# SR_latch.net
KiCad netlist of a schematic drawn in EAGLE
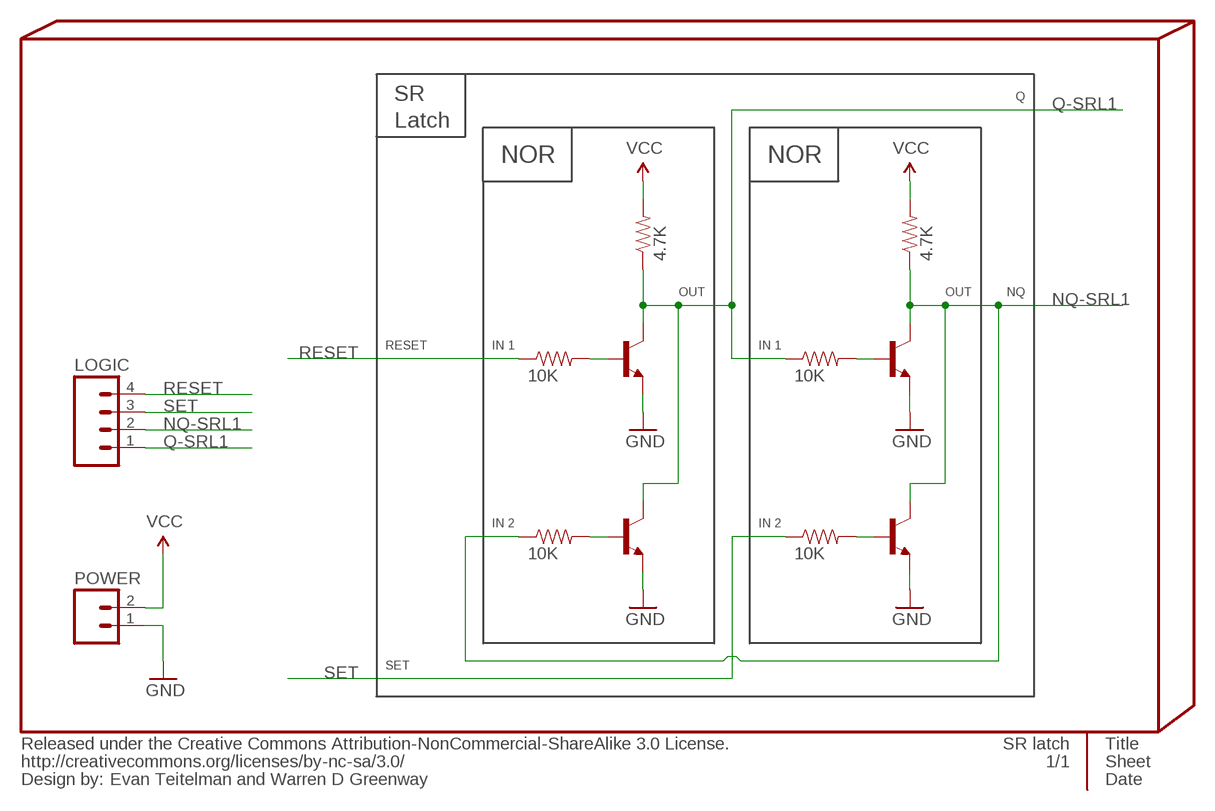
[diagram p0: schematic, sheet 1]

(export (version "E")
  (design (tool "Eeschema 10.0.6"))
  (components
    (comp (ref "INFO4")
      (value "Evan Teitelman and Warren D Greenway")
      (footprint "eagle-import:%CC-NC-SA")
      (libsource (lib "eagle-import") (part "%CC-NC-SA"))
    )
    (comp (ref "LOGIC")
      (value "M04PTH")
      (footprint "eagle-import:1X04")
      (libsource (lib "eagle-import") (part "M04PTH"))
    )
    (comp (ref "POWER")
      (value "M02PTH")
      (footprint "eagle-import:1X02")
      (libsource (lib "eagle-import") (part "M02PTH"))
    )
    (comp (ref "PUR-NOR1-SRL1")
      (value "4.7K")
      (footprint "eagle-import:0402-RES")
      (libsource (lib "eagle-import") (part "RESISTOR0402-RES"))
    )
    (comp (ref "PUR-NOR2-SRL1")
      (value "4.7K")
      (footprint "eagle-import:0402-RES")
      (libsource (lib "eagle-import") (part "RESISTOR0402-RES"))
    )
    (comp (ref "Q1-NOR1-SRL1")
      (value "TRANSISTOR_NPNSOT23")
      (footprint "eagle-import:SOT23")
      (libsource (lib "eagle-import") (part "TRANSISTOR_NPNSOT23"))
    )
    (comp (ref "Q1-NOR2-SRL1")
      (value "TRANSISTOR_NPNSOT23")
      (footprint "eagle-import:SOT23")
      (libsource (lib "eagle-import") (part "TRANSISTOR_NPNSOT23"))
    )
    (comp (ref "Q2-NOR1-SRL1")
      (value "TRANSISTOR_NPNSOT23")
      (footprint "eagle-import:SOT23")
      (libsource (lib "eagle-import") (part "TRANSISTOR_NPNSOT23"))
    )
    (comp (ref "Q2-NOR2-SRL1")
      (value "TRANSISTOR_NPNSOT23")
      (footprint "eagle-import:SOT23")
      (libsource (lib "eagle-import") (part "TRANSISTOR_NPNSOT23"))
    )
    (comp (ref "R1-NOR1-SRL1")
      (value "10K")
      (footprint "eagle-import:0402-RES")
      (libsource (lib "eagle-import") (part "RESISTOR0402-RES"))
    )
    (comp (ref "R1-NOR2-SRL1")
      (value "10K")
      (footprint "eagle-import:0402-RES")
      (libsource (lib "eagle-import") (part "RESISTOR0402-RES"))
    )
    (comp (ref "R2-NOR1-SRL1")
      (value "10K")
      (footprint "eagle-import:0402-RES")
      (libsource (lib "eagle-import") (part "RESISTOR0402-RES"))
    )
    (comp (ref "R2-NOR2-SRL1")
      (value "10K")
      (footprint "eagle-import:0402-RES")
      (libsource (lib "eagle-import") (part "RESISTOR0402-RES"))
    )
  )
  (nets
    (net (code "1") (name "/NQ-SRL1") (class "Default")
      (node (ref "LOGIC") (pin "2") (pinfunction "2_2") (pintype "passive"))
      (node (ref "PUR-NOR1-SRL1") (pin "1") (pinfunction "1_1") (pintype "passive"))
      (node (ref "Q1-NOR1-SRL1") (pin "3") (pinfunction "C_3") (pintype "passive"))
      (node (ref "Q2-NOR1-SRL1") (pin "3") (pinfunction "C_3") (pintype "passive"))
      (node (ref "R2-NOR2-SRL1") (pin "1") (pinfunction "1_1") (pintype "passive"))
    )
    (net (code "2") (name "/Q-SRL1") (class "Default")
      (node (ref "LOGIC") (pin "1") (pinfunction "1_1") (pintype "passive"))
      (node (ref "PUR-NOR2-SRL1") (pin "1") (pinfunction "1_1") (pintype "passive"))
      (node (ref "Q1-NOR2-SRL1") (pin "3") (pinfunction "C_3") (pintype "passive"))
      (node (ref "Q2-NOR2-SRL1") (pin "3") (pinfunction "C_3") (pintype "passive"))
      (node (ref "R1-NOR1-SRL1") (pin "1") (pinfunction "1_1") (pintype "passive"))
    )
    (net (code "3") (name "/RESET") (class "Default")
      (node (ref "LOGIC") (pin "4") (pinfunction "4_4") (pintype "passive"))
      (node (ref "R1-NOR2-SRL1") (pin "1") (pinfunction "1_1") (pintype "passive"))
    )
    (net (code "4") (name "/SET") (class "Default")
      (node (ref "LOGIC") (pin "3") (pinfunction "3_3") (pintype "passive"))
      (node (ref "R2-NOR1-SRL1") (pin "1") (pinfunction "1_1") (pintype "passive"))
    )
    (net (code "5") (name "@GND") (class "Default")
      (node (ref "POWER") (pin "1") (pinfunction "1_1") (pintype "passive"))
      (node (ref "Q1-NOR1-SRL1") (pin "2") (pinfunction "E_2") (pintype "passive"))
      (node (ref "Q1-NOR2-SRL1") (pin "2") (pinfunction "E_2") (pintype "passive"))
      (node (ref "Q2-NOR1-SRL1") (pin "2") (pinfunction "E_2") (pintype "passive"))
      (node (ref "Q2-NOR2-SRL1") (pin "2") (pinfunction "E_2") (pintype "passive"))
    )
    (net (code "6") (name "@VCC") (class "Default")
      (node (ref "POWER") (pin "2") (pinfunction "2_2") (pintype "passive"))
      (node (ref "PUR-NOR1-SRL1") (pin "2") (pinfunction "2_2") (pintype "passive"))
      (node (ref "PUR-NOR2-SRL1") (pin "2") (pinfunction "2_2") (pintype "passive"))
    )
    (net (code "7") (name "Net-(Q1-NOR1-SRL1-B)") (class "Default")
      (node (ref "Q1-NOR1-SRL1") (pin "1") (pinfunction "B_1") (pintype "passive"))
      (node (ref "R1-NOR1-SRL1") (pin "2") (pinfunction "2_2") (pintype "passive"))
    )
    (net (code "8") (name "Net-(Q1-NOR2-SRL1-B)") (class "Default")
      (node (ref "Q1-NOR2-SRL1") (pin "1") (pinfunction "B_1") (pintype "passive"))
      (node (ref "R1-NOR2-SRL1") (pin "2") (pinfunction "2_2") (pintype "passive"))
    )
    (net (code "9") (name "Net-(Q2-NOR1-SRL1-B)") (class "Default")
      (node (ref "Q2-NOR1-SRL1") (pin "1") (pinfunction "B_1") (pintype "passive"))
      (node (ref "R2-NOR1-SRL1") (pin "2") (pinfunction "2_2") (pintype "passive"))
    )
    (net (code "10") (name "Net-(Q2-NOR2-SRL1-B)") (class "Default")
      (node (ref "Q2-NOR2-SRL1") (pin "1") (pinfunction "B_1") (pintype "passive"))
      (node (ref "R2-NOR2-SRL1") (pin "2") (pinfunction "2_2") (pintype "passive"))
    )
  )
)
